# PiZero_breakout.net
KiCad netlist of a schematic drawn in EAGLE
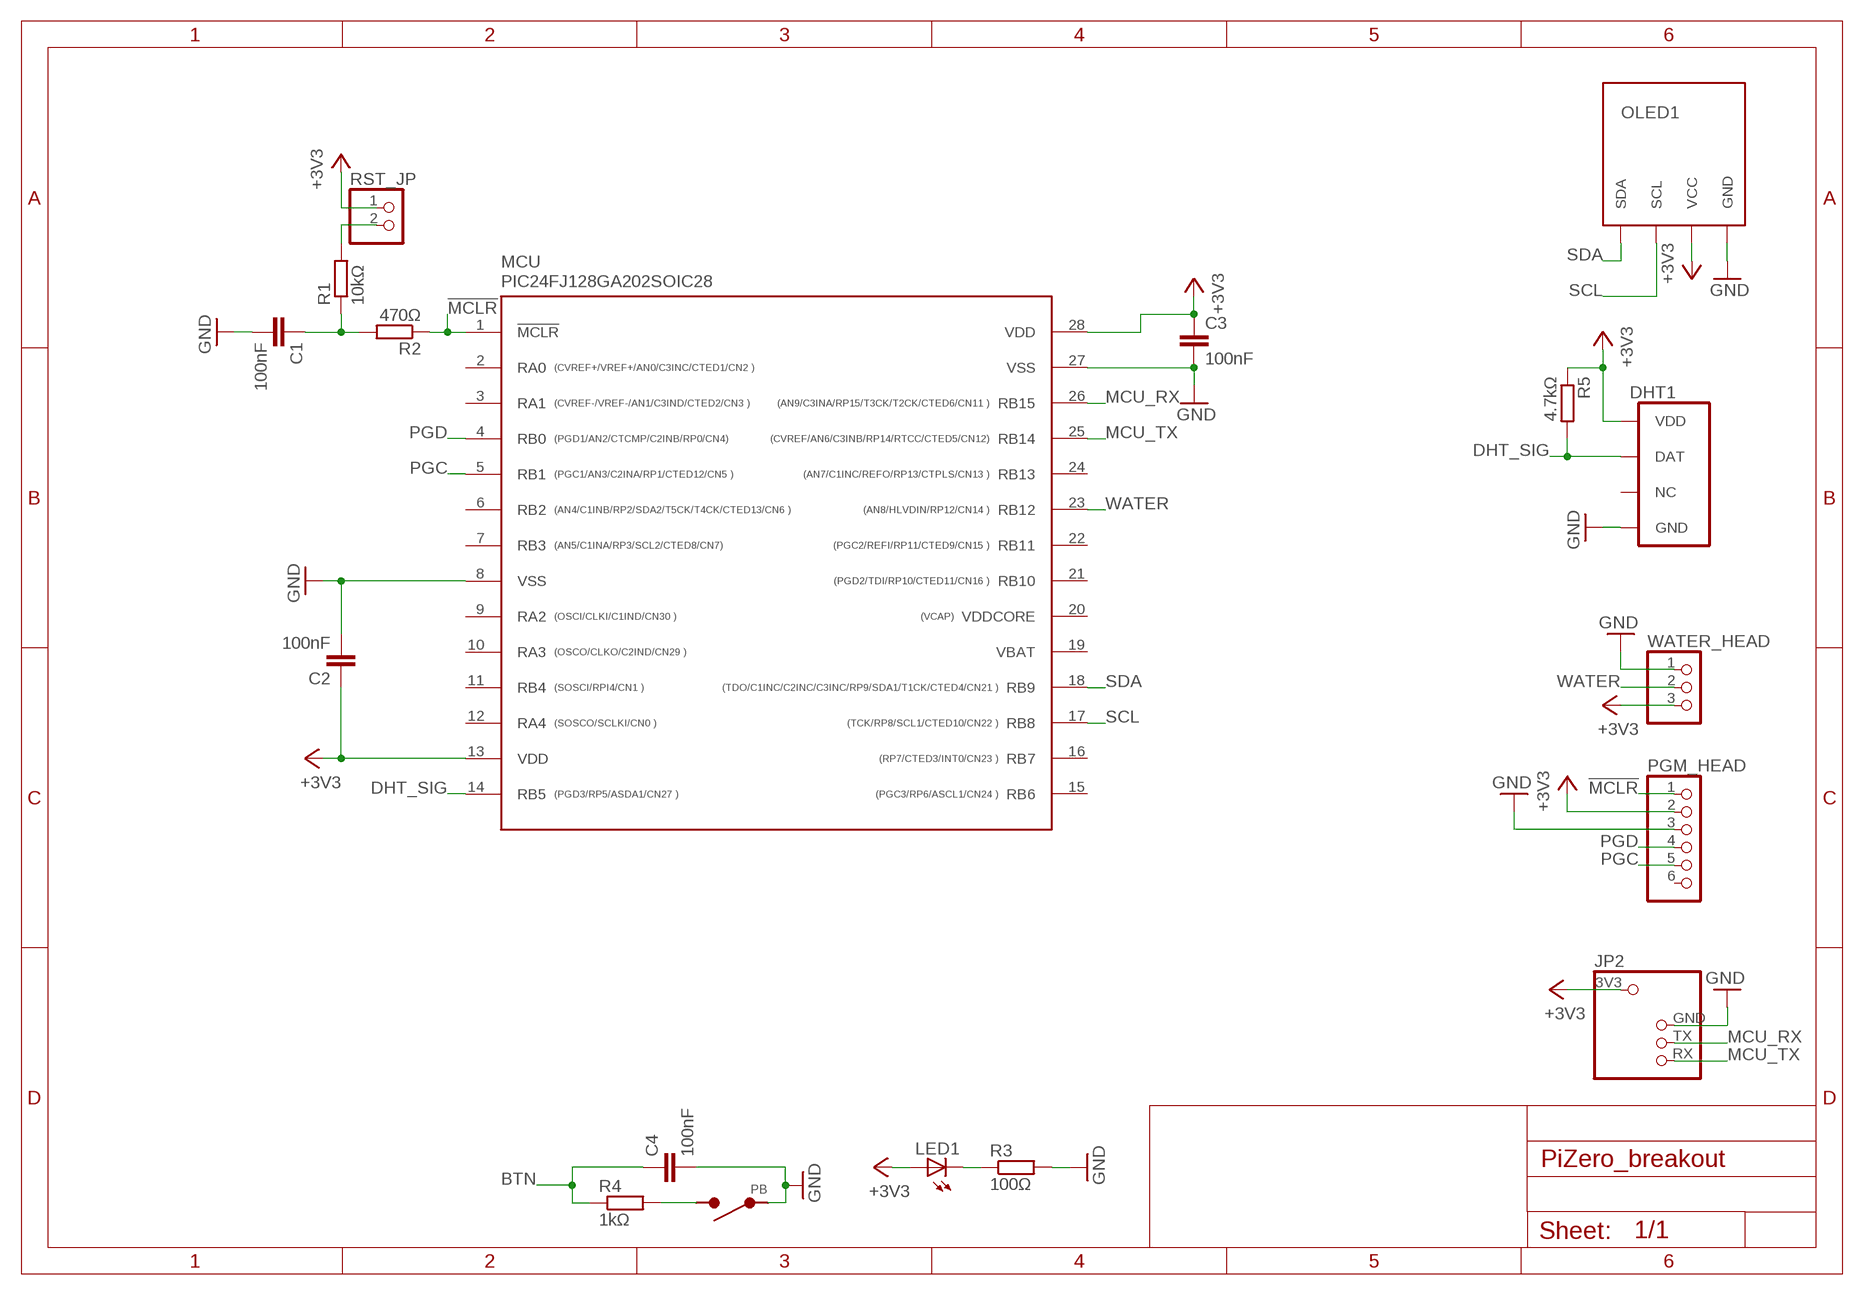
[diagram p0: schematic, sheet 1]

(export (version "E")
  (design (tool "Eeschema 10.0.6"))
  (components
    (comp (ref "C1")
      (value "100nF")
      (footprint "eagle-import:C0805")
      (libsource (lib "eagle-import") (part "C-EUC0805"))
    )
    (comp (ref "C2")
      (value "100nF")
      (footprint "eagle-import:C0805")
      (libsource (lib "eagle-import") (part "C-EUC0805"))
    )
    (comp (ref "C3")
      (value "100nF")
      (footprint "eagle-import:C0805")
      (libsource (lib "eagle-import") (part "C-EUC0805"))
    )
    (comp (ref "C4")
      (value "100nF")
      (footprint "eagle-import:C0805")
      (libsource (lib "eagle-import") (part "C-EUC0805"))
    )
    (comp (ref "DHT1")
      (value "DHT11VERT")
      (footprint "eagle-import:DHT11")
      (libsource (lib "eagle-import") (part "DHT11VERT"))
    )
    (comp (ref "JP2")
      (value "RPI_UART_HEADER")
      (footprint "eagle-import:RPI_UART_HEAD")
      (libsource (lib "eagle-import") (part "RPI_UART_HEADER"))
    )
    (comp (ref "LED1")
      (value "LEDCHIPLED_0805")
      (footprint "eagle-import:CHIPLED_0805")
      (libsource (lib "eagle-import") (part "LEDCHIPLED_0805"))
    )
    (comp (ref "MCU")
      (value "PIC24FJ128GA202SOIC28")
      (footprint "eagle-import:SOIC28L")
      (libsource (lib "eagle-import") (part "PIC24FJ128GA202SOIC28"))
    )
    (comp (ref "OLED1")
      (value "OLED_4PIN_I2C")
      (footprint "eagle-import:OLED_4PIN")
      (libsource (lib "eagle-import") (part "OLED_4PIN_I2C"))
    )
    (comp (ref "PB")
      (value "PUSHBUTTON_2LEG")
      (footprint "eagle-import:PUSHBUTTON_6X3.5MM")
      (libsource (lib "eagle-import") (part "PUSHBUTTON_2LEG"))
    )
    (comp (ref "PGM_HEAD")
      (value "PINHD-1X6")
      (footprint "eagle-import:1X06")
      (libsource (lib "eagle-import") (part "PINHD-1X6"))
    )
    (comp (ref "R1")
      (value "10kΩ")
      (footprint "eagle-import:R0805")
      (libsource (lib "eagle-import") (part "R-EU_R0805"))
    )
    (comp (ref "R2")
      (value "470Ω")
      (footprint "eagle-import:R0805")
      (libsource (lib "eagle-import") (part "R-EU_R0805"))
    )
    (comp (ref "R3")
      (value "100Ω")
      (footprint "eagle-import:R0805")
      (libsource (lib "eagle-import") (part "R-EU_R0805"))
    )
    (comp (ref "R4")
      (value "1kΩ")
      (footprint "eagle-import:R0805")
      (libsource (lib "eagle-import") (part "R-EU_R0805"))
    )
    (comp (ref "R5")
      (value "4.7kΩ")
      (footprint "eagle-import:R0805")
      (libsource (lib "eagle-import") (part "R-EU_R0805"))
    )
    (comp (ref "RST_JP")
      (value "PINHD-1X2")
      (footprint "eagle-import:1X02")
      (libsource (lib "eagle-import") (part "PINHD-1X2"))
    )
    (comp (ref "WATER_HEAD")
      (value "PINHD-1X3")
      (footprint "eagle-import:1X03")
      (libsource (lib "eagle-import") (part "PINHD-1X3"))
    )
  )
  (nets
    (net (code "1") (name "+3V3") (class "Default")
      (node (ref "C2") (pin "1") (pinfunction "1_1") (pintype "passive"))
      (node (ref "C3") (pin "1") (pinfunction "1_1") (pintype "passive"))
      (node (ref "DHT1") (pin "VDD") (pinfunction "VDD_VDD") (pintype "power_in"))
      (node (ref "JP2") (pin "3V3") (pinfunction "3V3_3V3") (pintype "passive"))
      (node (ref "LED1") (pin "A") (pinfunction "A_A") (pintype "passive"))
      (node (ref "MCU") (pin "13") (pinfunction "VDD_13") (pintype "power_in"))
      (node (ref "MCU") (pin "28") (pinfunction "VDD_28") (pintype "power_in"))
      (node (ref "OLED1") (pin "VCC") (pinfunction "VCC_VCC") (pintype "bidirectional"))
      (node (ref "PGM_HEAD") (pin "2") (pinfunction "2_2") (pintype "passive"))
      (node (ref "R5") (pin "1") (pinfunction "1_1") (pintype "passive"))
      (node (ref "RST_JP") (pin "1") (pinfunction "1_1") (pintype "passive"))
      (node (ref "WATER_HEAD") (pin "3") (pinfunction "3_3") (pintype "passive"))
    )
    (net (code "2") (name "/BTN") (class "Default")
      (node (ref "C4") (pin "1") (pinfunction "1_1") (pintype "passive"))
      (node (ref "R4") (pin "1") (pinfunction "1_1") (pintype "passive"))
    )
    (net (code "3") (name "/DHT_SIG") (class "Default")
      (node (ref "DHT1") (pin "DAT") (pinfunction "DAT_DAT") (pintype "bidirectional"))
      (node (ref "MCU") (pin "14") (pinfunction "RB5_14") (pintype "bidirectional"))
      (node (ref "R5") (pin "2") (pinfunction "2_2") (pintype "passive"))
    )
    (net (code "4") (name "/MCU_RX") (class "Default")
      (node (ref "JP2") (pin "TX") (pinfunction "TX_TX") (pintype "passive"))
      (node (ref "MCU") (pin "26") (pinfunction "RB15_26") (pintype "bidirectional"))
    )
    (net (code "5") (name "/MCU_TX") (class "Default")
      (node (ref "JP2") (pin "RX") (pinfunction "RX_RX") (pintype "passive"))
      (node (ref "MCU") (pin "25") (pinfunction "RB14_25") (pintype "bidirectional"))
    )
    (net (code "6") (name "/PGC") (class "Default")
      (node (ref "MCU") (pin "5") (pinfunction "RB1_5") (pintype "bidirectional"))
      (node (ref "PGM_HEAD") (pin "5") (pinfunction "5_5") (pintype "passive"))
    )
    (net (code "7") (name "/PGD") (class "Default")
      (node (ref "MCU") (pin "4") (pinfunction "RB0_4") (pintype "bidirectional"))
      (node (ref "PGM_HEAD") (pin "4") (pinfunction "4_4") (pintype "passive"))
    )
    (net (code "8") (name "/SCL") (class "Default")
      (node (ref "MCU") (pin "17") (pinfunction "RB8_17") (pintype "input"))
      (node (ref "OLED1") (pin "SCL") (pinfunction "SCL_SCL") (pintype "bidirectional"))
    )
    (net (code "9") (name "/SDA") (class "Default")
      (node (ref "MCU") (pin "18") (pinfunction "RB9_18") (pintype "output"))
      (node (ref "OLED1") (pin "SDA") (pinfunction "SDA_SDA") (pintype "bidirectional"))
    )
    (net (code "10") (name "/VDDCORE") (class "Default")
      (node (ref "MCU") (pin "20") (pinfunction "VDDCORE_20") (pintype "power_in"))
    )
    (net (code "11") (name "/WATER") (class "Default")
      (node (ref "MCU") (pin "23") (pinfunction "RB12_23") (pintype "bidirectional"))
      (node (ref "WATER_HEAD") (pin "2") (pinfunction "2_2") (pintype "passive"))
    )
    (net (code "12") (name "/~{MCLR}") (class "Default")
      (node (ref "MCU") (pin "1") (pinfunction "~{MCLR}_1") (pintype "bidirectional"))
      (node (ref "PGM_HEAD") (pin "1") (pinfunction "1_1") (pintype "passive"))
      (node (ref "R2") (pin "1") (pinfunction "1_1") (pintype "passive"))
    )
    (net (code "13") (name "GND") (class "Default")
      (node (ref "C1") (pin "2") (pinfunction "2_2") (pintype "passive"))
      (node (ref "C2") (pin "2") (pinfunction "2_2") (pintype "passive"))
      (node (ref "C3") (pin "2") (pinfunction "2_2") (pintype "passive"))
      (node (ref "C4") (pin "2") (pinfunction "2_2") (pintype "passive"))
      (node (ref "DHT1") (pin "GND") (pinfunction "GND_GND") (pintype "power_in"))
      (node (ref "JP2") (pin "GND") (pinfunction "GND_GND") (pintype "passive"))
      (node (ref "MCU") (pin "27") (pinfunction "VSS_27") (pintype "power_in"))
      (node (ref "MCU") (pin "8") (pinfunction "VSS_8") (pintype "power_in"))
      (node (ref "OLED1") (pin "GND") (pinfunction "GND_GND") (pintype "bidirectional"))
      (node (ref "PB") (pin "P$1") (pinfunction "P$1_P$1") (pintype "bidirectional"))
      (node (ref "PGM_HEAD") (pin "3") (pinfunction "3_3") (pintype "passive"))
      (node (ref "R3") (pin "2") (pinfunction "2_2") (pintype "passive"))
      (node (ref "WATER_HEAD") (pin "1") (pinfunction "1_1") (pintype "passive"))
    )
    (net (code "14") (name "Net-(C1-Pad1)") (class "Default")
      (node (ref "C1") (pin "1") (pinfunction "1_1") (pintype "passive"))
      (node (ref "R1") (pin "1") (pinfunction "1_1") (pintype "passive"))
      (node (ref "R2") (pin "2") (pinfunction "2_2") (pintype "passive"))
    )
    (net (code "15") (name "Net-(LED1-PadC)") (class "Default")
      (node (ref "LED1") (pin "C") (pinfunction "C_C") (pintype "passive"))
      (node (ref "R3") (pin "1") (pinfunction "1_1") (pintype "passive"))
    )
    (net (code "16") (name "Net-(PB-PadP$2)") (class "Default")
      (node (ref "PB") (pin "P$2") (pinfunction "P$2_P$2") (pintype "bidirectional"))
      (node (ref "R4") (pin "2") (pinfunction "2_2") (pintype "passive"))
    )
    (net (code "17") (name "Net-(R1-Pad2)") (class "Default")
      (node (ref "R1") (pin "2") (pinfunction "2_2") (pintype "passive"))
      (node (ref "RST_JP") (pin "2") (pinfunction "2_2") (pintype "passive"))
    )
    (net (code "18") (name "unconnected-(DHT1-PadNC)") (class "Default")
      (node (ref "DHT1") (pin "NC") (pinfunction "NC_NC") (pintype "no_connect"))
    )
    (net (code "19") (name "unconnected-(MCU-RA0-Pad2)") (class "Default")
      (node (ref "MCU") (pin "2") (pinfunction "RA0_2") (pintype "bidirectional"))
    )
    (net (code "20") (name "unconnected-(MCU-RA1-Pad3)") (class "Default")
      (node (ref "MCU") (pin "3") (pinfunction "RA1_3") (pintype "bidirectional"))
    )
    (net (code "21") (name "unconnected-(MCU-RA2-Pad9)") (class "Default")
      (node (ref "MCU") (pin "9") (pinfunction "RA2_9") (pintype "bidirectional"))
    )
    (net (code "22") (name "unconnected-(MCU-RA3-Pad10)") (class "Default")
      (node (ref "MCU") (pin "10") (pinfunction "RA3_10") (pintype "bidirectional"))
    )
    (net (code "23") (name "unconnected-(MCU-RA4-Pad12)") (class "Default")
      (node (ref "MCU") (pin "12") (pinfunction "RA4_12") (pintype "bidirectional"))
    )
    (net (code "24") (name "unconnected-(MCU-RB2-Pad6)") (class "Default")
      (node (ref "MCU") (pin "6") (pinfunction "RB2_6") (pintype "bidirectional"))
    )
    (net (code "25") (name "unconnected-(MCU-RB3-Pad7)") (class "Default")
      (node (ref "MCU") (pin "7") (pinfunction "RB3_7") (pintype "bidirectional"))
    )
    (net (code "26") (name "unconnected-(MCU-RB4-Pad11)") (class "Default")
      (node (ref "MCU") (pin "11") (pinfunction "RB4_11") (pintype "bidirectional"))
    )
    (net (code "27") (name "unconnected-(MCU-RB6-Pad15)") (class "Default")
      (node (ref "MCU") (pin "15") (pinfunction "RB6_15") (pintype "bidirectional"))
    )
    (net (code "28") (name "unconnected-(MCU-RB7-Pad16)") (class "Default")
      (node (ref "MCU") (pin "16") (pinfunction "RB7_16") (pintype "bidirectional"))
    )
    (net (code "29") (name "unconnected-(MCU-RB10-Pad21)") (class "Default")
      (node (ref "MCU") (pin "21") (pinfunction "RB10_21") (pintype "input"))
    )
    (net (code "30") (name "unconnected-(MCU-RB11-Pad22)") (class "Default")
      (node (ref "MCU") (pin "22") (pinfunction "RB11_22") (pintype "input"))
    )
    (net (code "31") (name "unconnected-(MCU-RB13-Pad24)") (class "Default")
      (node (ref "MCU") (pin "24") (pinfunction "RB13_24") (pintype "bidirectional"))
    )
    (net (code "32") (name "unconnected-(MCU-VBAT-Pad19)") (class "Default")
      (node (ref "MCU") (pin "19") (pinfunction "VBAT_19") (pintype "passive"))
    )
    (net (code "33") (name "unconnected-(PGM_HEAD-Pad6)") (class "Default")
      (node (ref "PGM_HEAD") (pin "6") (pinfunction "6_6") (pintype "passive"))
    )
  )
)
